# STOPBAND_FILTER.net
KiCad netlist of a schematic drawn in EAGLE
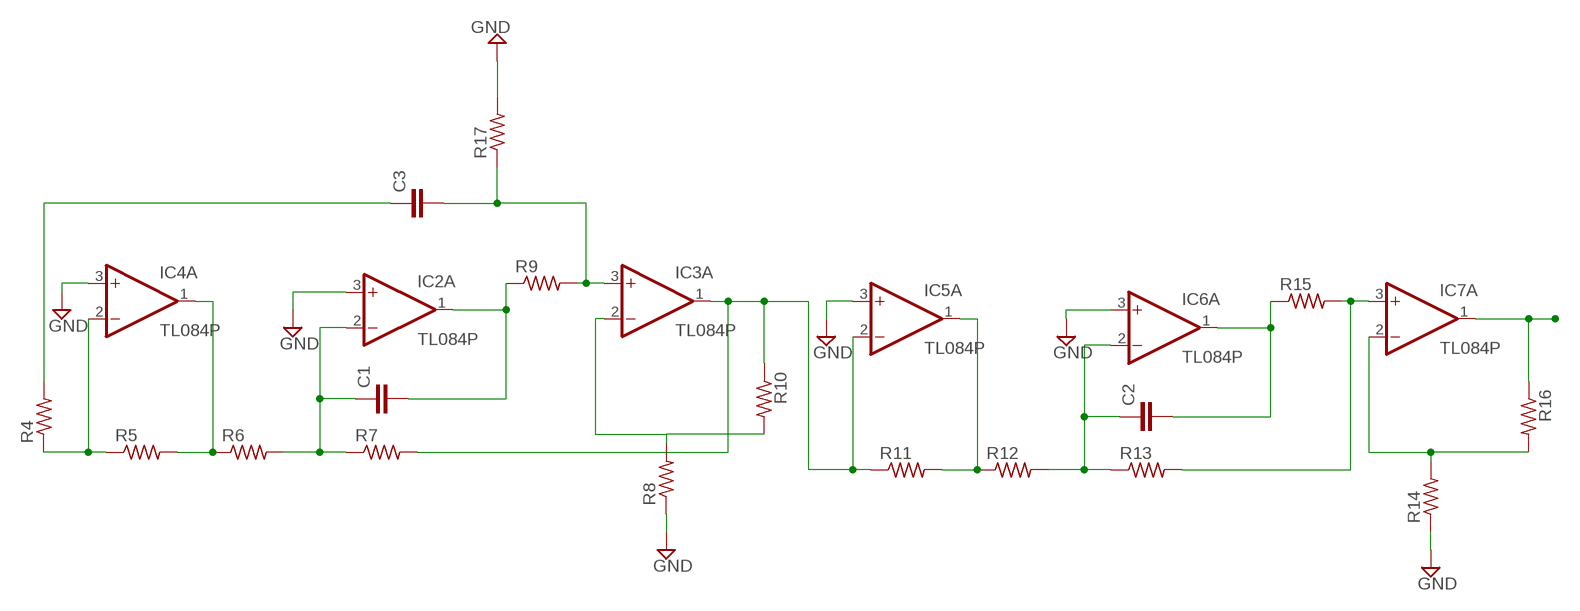
[diagram p0: schematic, sheet 1]

(export (version "E")
  (design (tool "Eeschema 10.0.6"))
  (components
    (comp (ref "C1")
      (value "C-EU050-030X075")
      (footprint "eagle-import:C050-030X075")
      (libsource (lib "eagle-import") (part "C-EU050-030X075"))
    )
    (comp (ref "C2")
      (value "C-EU050-030X075")
      (footprint "eagle-import:C050-030X075")
      (libsource (lib "eagle-import") (part "C-EU050-030X075"))
    )
    (comp (ref "C3")
      (value "C-EU050-030X075")
      (footprint "eagle-import:C050-030X075")
      (libsource (lib "eagle-import") (part "C-EU050-030X075"))
    )
    (comp (ref "IC2")
      (value "TL084P")
      (footprint "eagle-import:DIL14")
      (libsource (lib "eagle-import") (part "TL084P"))
    )
    (comp (ref "IC3")
      (value "TL084P")
      (footprint "eagle-import:DIL14")
      (libsource (lib "eagle-import") (part "TL084P"))
    )
    (comp (ref "IC4")
      (value "TL084P")
      (footprint "eagle-import:DIL14")
      (libsource (lib "eagle-import") (part "TL084P"))
    )
    (comp (ref "IC5")
      (value "TL084P")
      (footprint "eagle-import:DIL14")
      (libsource (lib "eagle-import") (part "TL084P"))
    )
    (comp (ref "IC6")
      (value "TL084P")
      (footprint "eagle-import:DIL14")
      (libsource (lib "eagle-import") (part "TL084P"))
    )
    (comp (ref "IC7")
      (value "TL084P")
      (footprint "eagle-import:DIL14")
      (libsource (lib "eagle-import") (part "TL084P"))
    )
    (comp (ref "R4")
      (value "R-US_0204/5")
      (footprint "eagle-import:0204_5")
      (libsource (lib "eagle-import") (part "R-US_0204/5"))
    )
    (comp (ref "R5")
      (value "R-US_0204/5")
      (footprint "eagle-import:0204_5")
      (libsource (lib "eagle-import") (part "R-US_0204/5"))
    )
    (comp (ref "R6")
      (value "R-US_0204/5")
      (footprint "eagle-import:0204_5")
      (libsource (lib "eagle-import") (part "R-US_0204/5"))
    )
    (comp (ref "R7")
      (value "R-US_0204/5")
      (footprint "eagle-import:0204_5")
      (libsource (lib "eagle-import") (part "R-US_0204/5"))
    )
    (comp (ref "R8")
      (value "R-US_0204/5")
      (footprint "eagle-import:0204_5")
      (libsource (lib "eagle-import") (part "R-US_0204/5"))
    )
    (comp (ref "R9")
      (value "R-US_0204/5")
      (footprint "eagle-import:0204_5")
      (libsource (lib "eagle-import") (part "R-US_0204/5"))
    )
    (comp (ref "R10")
      (value "R-US_0204/5")
      (footprint "eagle-import:0204_5")
      (libsource (lib "eagle-import") (part "R-US_0204/5"))
    )
    (comp (ref "R11")
      (value "R-US_0204/5")
      (footprint "eagle-import:0204_5")
      (libsource (lib "eagle-import") (part "R-US_0204/5"))
    )
    (comp (ref "R12")
      (value "R-US_0204/5")
      (footprint "eagle-import:0204_5")
      (libsource (lib "eagle-import") (part "R-US_0204/5"))
    )
    (comp (ref "R13")
      (value "R-US_0204/5")
      (footprint "eagle-import:0204_5")
      (libsource (lib "eagle-import") (part "R-US_0204/5"))
    )
    (comp (ref "R14")
      (value "R-US_0204/5")
      (footprint "eagle-import:0204_5")
      (libsource (lib "eagle-import") (part "R-US_0204/5"))
    )
    (comp (ref "R15")
      (value "R-US_0204/5")
      (footprint "eagle-import:0204_5")
      (libsource (lib "eagle-import") (part "R-US_0204/5"))
    )
    (comp (ref "R16")
      (value "R-US_0204/5")
      (footprint "eagle-import:0204_5")
      (libsource (lib "eagle-import") (part "R-US_0204/5"))
    )
    (comp (ref "R17")
      (value "R-US_0204/5")
      (footprint "eagle-import:0204_5")
      (libsource (lib "eagle-import") (part "R-US_0204/5"))
    )
  )
  (nets
    (net (code "1") (name "GND") (class "Default")
      (node (ref "IC2") (pin "3") (pinfunction "+IN_3") (pintype "input"))
      (node (ref "IC4") (pin "3") (pinfunction "+IN_3") (pintype "input"))
      (node (ref "IC5") (pin "3") (pinfunction "+IN_3") (pintype "input"))
      (node (ref "IC6") (pin "3") (pinfunction "+IN_3") (pintype "input"))
      (node (ref "R14") (pin "1") (pinfunction "1_1") (pintype "passive"))
      (node (ref "R17") (pin "2") (pinfunction "2_2") (pintype "passive"))
      (node (ref "R8") (pin "1") (pinfunction "1_1") (pintype "passive"))
    )
    (net (code "2") (name "Net-(C3-Pad1)") (class "Default")
      (node (ref "C3") (pin "1") (pinfunction "1_1") (pintype "passive"))
      (node (ref "R4") (pin "2") (pinfunction "2_2") (pintype "passive"))
    )
    (net (code "3") (name "Net-(IC2A--IN)") (class "Default")
      (node (ref "C1") (pin "1") (pinfunction "1_1") (pintype "passive"))
      (node (ref "IC2") (pin "2") (pinfunction "-IN_2") (pintype "input"))
      (node (ref "R6") (pin "2") (pinfunction "2_2") (pintype "passive"))
      (node (ref "R7") (pin "1") (pinfunction "1_1") (pintype "passive"))
    )
    (net (code "4") (name "Net-(IC2A-OUT)") (class "Default")
      (node (ref "C1") (pin "2") (pinfunction "2_2") (pintype "passive"))
      (node (ref "IC2") (pin "1") (pinfunction "OUT_1") (pintype "output"))
      (node (ref "R9") (pin "1") (pinfunction "1_1") (pintype "passive"))
    )
    (net (code "5") (name "Net-(IC3A-+IN)") (class "Default")
      (node (ref "C3") (pin "2") (pinfunction "2_2") (pintype "passive"))
      (node (ref "IC3") (pin "3") (pinfunction "+IN_3") (pintype "input"))
      (node (ref "R17") (pin "1") (pinfunction "1_1") (pintype "passive"))
      (node (ref "R9") (pin "2") (pinfunction "2_2") (pintype "passive"))
    )
    (net (code "6") (name "Net-(IC3A--IN)") (class "Default")
      (node (ref "IC3") (pin "2") (pinfunction "-IN_2") (pintype "input"))
      (node (ref "R10") (pin "2") (pinfunction "2_2") (pintype "passive"))
      (node (ref "R8") (pin "2") (pinfunction "2_2") (pintype "passive"))
    )
    (net (code "7") (name "Net-(IC3A-OUT)") (class "Default")
      (node (ref "IC3") (pin "1") (pinfunction "OUT_1") (pintype "output"))
      (node (ref "IC5") (pin "2") (pinfunction "-IN_2") (pintype "input"))
      (node (ref "R10") (pin "1") (pinfunction "1_1") (pintype "passive"))
      (node (ref "R11") (pin "1") (pinfunction "1_1") (pintype "passive"))
      (node (ref "R7") (pin "2") (pinfunction "2_2") (pintype "passive"))
    )
    (net (code "8") (name "Net-(IC4A--IN)") (class "Default")
      (node (ref "IC4") (pin "2") (pinfunction "-IN_2") (pintype "input"))
      (node (ref "R4") (pin "1") (pinfunction "1_1") (pintype "passive"))
      (node (ref "R5") (pin "1") (pinfunction "1_1") (pintype "passive"))
    )
    (net (code "9") (name "Net-(IC4A-OUT)") (class "Default")
      (node (ref "IC4") (pin "1") (pinfunction "OUT_1") (pintype "output"))
      (node (ref "R5") (pin "2") (pinfunction "2_2") (pintype "passive"))
      (node (ref "R6") (pin "1") (pinfunction "1_1") (pintype "passive"))
    )
    (net (code "10") (name "Net-(IC5A-OUT)") (class "Default")
      (node (ref "IC5") (pin "1") (pinfunction "OUT_1") (pintype "output"))
      (node (ref "R11") (pin "2") (pinfunction "2_2") (pintype "passive"))
      (node (ref "R12") (pin "1") (pinfunction "1_1") (pintype "passive"))
    )
    (net (code "11") (name "Net-(IC6A--IN)") (class "Default")
      (node (ref "C2") (pin "1") (pinfunction "1_1") (pintype "passive"))
      (node (ref "IC6") (pin "2") (pinfunction "-IN_2") (pintype "input"))
      (node (ref "R12") (pin "2") (pinfunction "2_2") (pintype "passive"))
      (node (ref "R13") (pin "1") (pinfunction "1_1") (pintype "passive"))
    )
    (net (code "12") (name "Net-(IC6A-OUT)") (class "Default")
      (node (ref "C2") (pin "2") (pinfunction "2_2") (pintype "passive"))
      (node (ref "IC6") (pin "1") (pinfunction "OUT_1") (pintype "output"))
      (node (ref "R15") (pin "1") (pinfunction "1_1") (pintype "passive"))
    )
    (net (code "13") (name "Net-(IC7A-+IN)") (class "Default")
      (node (ref "IC7") (pin "3") (pinfunction "+IN_3") (pintype "input"))
      (node (ref "R13") (pin "2") (pinfunction "2_2") (pintype "passive"))
      (node (ref "R15") (pin "2") (pinfunction "2_2") (pintype "passive"))
    )
    (net (code "14") (name "Net-(IC7A--IN)") (class "Default")
      (node (ref "IC7") (pin "2") (pinfunction "-IN_2") (pintype "input"))
      (node (ref "R14") (pin "2") (pinfunction "2_2") (pintype "passive"))
      (node (ref "R16") (pin "2") (pinfunction "2_2") (pintype "passive"))
    )
    (net (code "15") (name "Net-(IC7A-OUT)") (class "Default")
      (node (ref "IC7") (pin "1") (pinfunction "OUT_1") (pintype "output"))
      (node (ref "R16") (pin "1") (pinfunction "1_1") (pintype "passive"))
    )
  )
)
